# ADC_1_MUL.net
KiCad netlist of a schematic drawn in Altium Designer
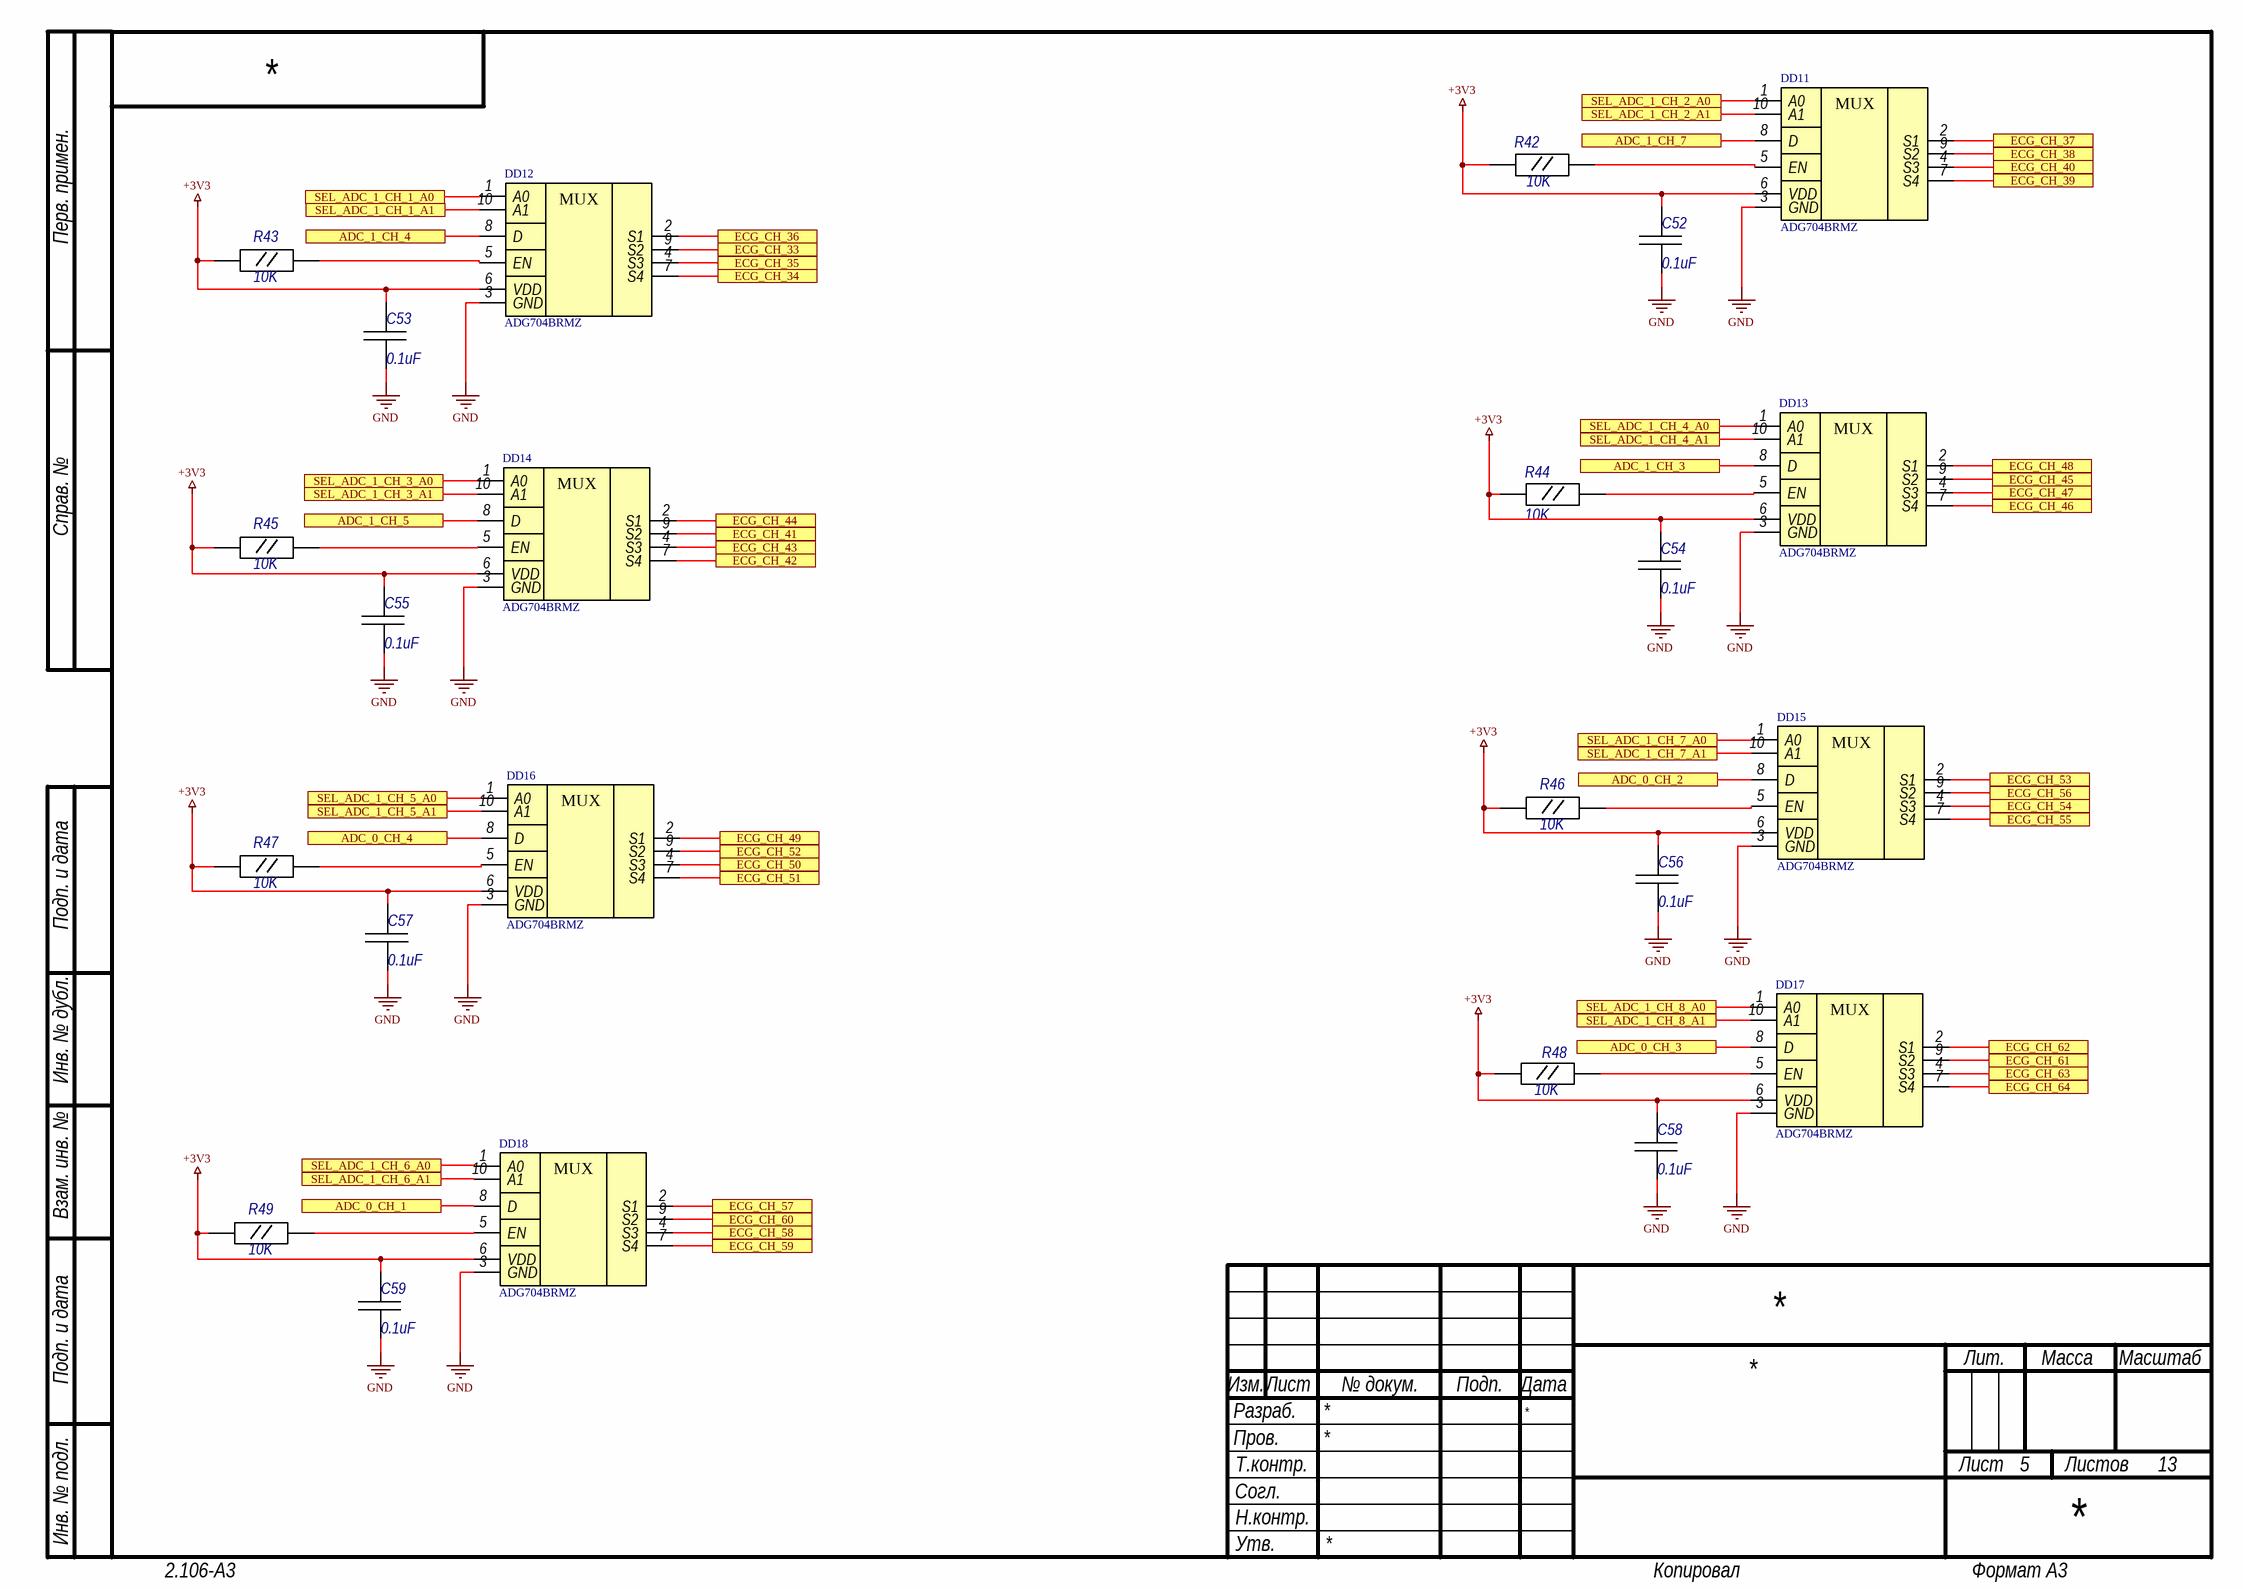
[diagram p0: ADC_1_MUL.SchDoc]

(export (version "E")
  (design (tool "Eeschema 10.0.6"))
  (components
    (comp (ref "C52")
      (value "0.1uF")
      (footprint "C0603")
      (description "Ceramic Capacitor SMD")
      (libsource (lib "") (part "CC_SMD_0603_1"))
    )
    (comp (ref "C53")
      (value "0.1uF")
      (footprint "C0603")
      (description "Ceramic Capacitor SMD")
      (libsource (lib "GOST") (part "CC_SMD_0603"))
    )
    (comp (ref "C54")
      (value "0.1uF")
      (footprint "C0603")
      (description "Ceramic Capacitor SMD")
      (libsource (lib "") (part "CC_SMD_0603_1"))
    )
    (comp (ref "C55")
      (value "0.1uF")
      (footprint "C0603")
      (description "Ceramic Capacitor SMD")
      (libsource (lib "GOST") (part "CC_SMD_0603"))
    )
    (comp (ref "C56")
      (value "0.1uF")
      (footprint "C0603")
      (description "Ceramic Capacitor SMD")
      (libsource (lib "GOST") (part "CC_SMD_0603"))
    )
    (comp (ref "C57")
      (value "0.1uF")
      (footprint "C0603")
      (description "Ceramic Capacitor SMD")
      (libsource (lib "GOST") (part "CC_SMD_0603"))
    )
    (comp (ref "C58")
      (value "0.1uF")
      (footprint "C0603")
      (description "Ceramic Capacitor SMD")
      (libsource (lib "GOST") (part "CC_SMD_0603"))
    )
    (comp (ref "C59")
      (value "0.1uF")
      (footprint "C0603")
      (description "Ceramic Capacitor SMD")
      (libsource (lib "GOST") (part "CC_SMD_0603"))
    )
    (comp (ref "DD11")
      (value "ADG704BRMZ")
      (footprint "MSOP-10")
      (description "4-Channel Multiplexer")
      (libsource (lib "GOST") (part "MUX_ADG704BRMZ"))
    )
    (comp (ref "DD12")
      (value "ADG704BRMZ")
      (footprint "MSOP-10")
      (description "4-Channel Multiplexer")
      (libsource (lib "GOST") (part "MUX_ADG704BRMZ"))
    )
    (comp (ref "DD13")
      (value "ADG704BRMZ")
      (footprint "MSOP-10")
      (description "4-Channel Multiplexer")
      (libsource (lib "GOST") (part "MUX_ADG704BRMZ"))
    )
    (comp (ref "DD14")
      (value "ADG704BRMZ")
      (footprint "MSOP-10")
      (description "4-Channel Multiplexer")
      (libsource (lib "GOST") (part "MUX_ADG704BRMZ"))
    )
    (comp (ref "DD15")
      (value "ADG704BRMZ")
      (footprint "MSOP-10")
      (description "4-Channel Multiplexer")
      (libsource (lib "GOST") (part "MUX_ADG704BRMZ"))
    )
    (comp (ref "DD16")
      (value "ADG704BRMZ")
      (footprint "MSOP-10")
      (description "4-Channel Multiplexer")
      (libsource (lib "GOST") (part "MUX_ADG704BRMZ"))
    )
    (comp (ref "DD17")
      (value "ADG704BRMZ")
      (footprint "MSOP-10")
      (description "4-Channel Multiplexer")
      (libsource (lib "GOST") (part "MUX_ADG704BRMZ"))
    )
    (comp (ref "DD18")
      (value "ADG704BRMZ")
      (footprint "MSOP-10")
      (description "4-Channel Multiplexer")
      (libsource (lib "GOST") (part "MUX_ADG704BRMZ"))
    )
    (comp (ref "R42")
      (value "10K")
      (footprint "R0603")
      (description "Resistor SMD")
      (libsource (lib "") (part "R0603_1"))
    )
    (comp (ref "R43")
      (value "10K")
      (footprint "R0603")
      (description "Resistor SMD")
      (libsource (lib "") (part "R0603_1"))
    )
    (comp (ref "R44")
      (value "10K")
      (footprint "R0603")
      (description "Resistor SMD")
      (libsource (lib "") (part "R0603_1"))
    )
    (comp (ref "R45")
      (value "10K")
      (footprint "R0603")
      (description "Resistor SMD")
      (libsource (lib "") (part "R0603_1"))
    )
    (comp (ref "R46")
      (value "10K")
      (footprint "R0603")
      (description "Resistor SMD")
      (libsource (lib "GOST") (part "R0603"))
    )
    (comp (ref "R47")
      (value "10K")
      (footprint "R0603")
      (description "Resistor SMD")
      (libsource (lib "GOST") (part "R0603"))
    )
    (comp (ref "R48")
      (value "10K")
      (footprint "R0603")
      (description "Resistor SMD")
      (libsource (lib "GOST") (part "R0603"))
    )
    (comp (ref "R49")
      (value "10K")
      (footprint "R0603")
      (description "Resistor SMD")
      (libsource (lib "GOST") (part "R0603"))
    )
  )
  (nets
    (net (code "1") (name "+3V3") (class "Default")
      (node (ref "C52") (pin "2") (pinfunction "2_2") (pintype "passive"))
      (node (ref "C53") (pin "2") (pinfunction "2_2") (pintype "passive"))
      (node (ref "C54") (pin "2") (pinfunction "2_2") (pintype "passive"))
      (node (ref "C55") (pin "2") (pinfunction "2_2") (pintype "passive"))
      (node (ref "C56") (pin "2") (pinfunction "2_2") (pintype "passive"))
      (node (ref "C57") (pin "2") (pinfunction "2_2") (pintype "passive"))
      (node (ref "C58") (pin "2") (pinfunction "2_2") (pintype "passive"))
      (node (ref "C59") (pin "2") (pinfunction "2_2") (pintype "passive"))
      (node (ref "DD11") (pin "6") (pinfunction "VDD_6") (pintype "passive"))
      (node (ref "DD12") (pin "6") (pinfunction "VDD_6") (pintype "passive"))
      (node (ref "DD13") (pin "6") (pinfunction "VDD_6") (pintype "passive"))
      (node (ref "DD14") (pin "6") (pinfunction "VDD_6") (pintype "passive"))
      (node (ref "DD15") (pin "6") (pinfunction "VDD_6") (pintype "passive"))
      (node (ref "DD16") (pin "6") (pinfunction "VDD_6") (pintype "passive"))
      (node (ref "DD17") (pin "6") (pinfunction "VDD_6") (pintype "passive"))
      (node (ref "DD18") (pin "6") (pinfunction "VDD_6") (pintype "passive"))
      (node (ref "R42") (pin "1") (pinfunction "1_1") (pintype "passive"))
      (node (ref "R43") (pin "1") (pinfunction "1_1") (pintype "passive"))
      (node (ref "R44") (pin "1") (pinfunction "1_1") (pintype "passive"))
      (node (ref "R45") (pin "1") (pinfunction "1_1") (pintype "passive"))
      (node (ref "R46") (pin "1") (pinfunction "1_1") (pintype "passive"))
      (node (ref "R47") (pin "1") (pinfunction "1_1") (pintype "passive"))
      (node (ref "R48") (pin "1") (pinfunction "1_1") (pintype "passive"))
      (node (ref "R49") (pin "1") (pinfunction "1_1") (pintype "passive"))
    )
    (net (code "2") (name "/ADC_0_CH_1") (class "Default")
      (node (ref "DD18") (pin "8") (pinfunction "D_8") (pintype "passive"))
    )
    (net (code "3") (name "/ADC_0_CH_2") (class "Default")
      (node (ref "DD15") (pin "8") (pinfunction "D_8") (pintype "passive"))
    )
    (net (code "4") (name "/ADC_0_CH_3") (class "Default")
      (node (ref "DD17") (pin "8") (pinfunction "D_8") (pintype "passive"))
    )
    (net (code "5") (name "/ADC_0_CH_4") (class "Default")
      (node (ref "DD16") (pin "8") (pinfunction "D_8") (pintype "passive"))
    )
    (net (code "6") (name "/ADC_1_CH_3") (class "Default")
      (node (ref "DD13") (pin "8") (pinfunction "D_8") (pintype "passive"))
    )
    (net (code "7") (name "/ADC_1_CH_4") (class "Default")
      (node (ref "DD12") (pin "8") (pinfunction "D_8") (pintype "passive"))
    )
    (net (code "8") (name "/ADC_1_CH_5") (class "Default")
      (node (ref "DD14") (pin "8") (pinfunction "D_8") (pintype "passive"))
    )
    (net (code "9") (name "/ADC_1_CH_7") (class "Default")
      (node (ref "DD11") (pin "8") (pinfunction "D_8") (pintype "passive"))
    )
    (net (code "10") (name "/ECG_CH_33") (class "Default")
      (node (ref "DD12") (pin "9") (pinfunction "S2_9") (pintype "passive"))
    )
    (net (code "11") (name "/ECG_CH_34") (class "Default")
      (node (ref "DD12") (pin "7") (pinfunction "S4_7") (pintype "passive"))
    )
    (net (code "12") (name "/ECG_CH_35") (class "Default")
      (node (ref "DD12") (pin "4") (pinfunction "S3_4") (pintype "passive"))
    )
    (net (code "13") (name "/ECG_CH_36") (class "Default")
      (node (ref "DD12") (pin "2") (pinfunction "S1_2") (pintype "passive"))
    )
    (net (code "14") (name "/ECG_CH_37") (class "Default")
      (node (ref "DD11") (pin "2") (pinfunction "S1_2") (pintype "passive"))
    )
    (net (code "15") (name "/ECG_CH_38") (class "Default")
      (node (ref "DD11") (pin "9") (pinfunction "S2_9") (pintype "passive"))
    )
    (net (code "16") (name "/ECG_CH_39") (class "Default")
      (node (ref "DD11") (pin "7") (pinfunction "S4_7") (pintype "passive"))
    )
    (net (code "17") (name "/ECG_CH_40") (class "Default")
      (node (ref "DD11") (pin "4") (pinfunction "S3_4") (pintype "passive"))
    )
    (net (code "18") (name "/ECG_CH_41") (class "Default")
      (node (ref "DD14") (pin "9") (pinfunction "S2_9") (pintype "passive"))
    )
    (net (code "19") (name "/ECG_CH_42") (class "Default")
      (node (ref "DD14") (pin "7") (pinfunction "S4_7") (pintype "passive"))
    )
    (net (code "20") (name "/ECG_CH_43") (class "Default")
      (node (ref "DD14") (pin "4") (pinfunction "S3_4") (pintype "passive"))
    )
    (net (code "21") (name "/ECG_CH_44") (class "Default")
      (node (ref "DD14") (pin "2") (pinfunction "S1_2") (pintype "passive"))
    )
    (net (code "22") (name "/ECG_CH_45") (class "Default")
      (node (ref "DD13") (pin "9") (pinfunction "S2_9") (pintype "passive"))
    )
    (net (code "23") (name "/ECG_CH_46") (class "Default")
      (node (ref "DD13") (pin "7") (pinfunction "S4_7") (pintype "passive"))
    )
    (net (code "24") (name "/ECG_CH_47") (class "Default")
      (node (ref "DD13") (pin "4") (pinfunction "S3_4") (pintype "passive"))
    )
    (net (code "25") (name "/ECG_CH_48") (class "Default")
      (node (ref "DD13") (pin "2") (pinfunction "S1_2") (pintype "passive"))
    )
    (net (code "26") (name "/ECG_CH_49") (class "Default")
      (node (ref "DD16") (pin "2") (pinfunction "S1_2") (pintype "passive"))
    )
    (net (code "27") (name "/ECG_CH_50") (class "Default")
      (node (ref "DD16") (pin "4") (pinfunction "S3_4") (pintype "passive"))
    )
    (net (code "28") (name "/ECG_CH_51") (class "Default")
      (node (ref "DD16") (pin "7") (pinfunction "S4_7") (pintype "passive"))
    )
    (net (code "29") (name "/ECG_CH_52") (class "Default")
      (node (ref "DD16") (pin "9") (pinfunction "S2_9") (pintype "passive"))
    )
    (net (code "30") (name "/ECG_CH_53") (class "Default")
      (node (ref "DD15") (pin "2") (pinfunction "S1_2") (pintype "passive"))
    )
    (net (code "31") (name "/ECG_CH_54") (class "Default")
      (node (ref "DD15") (pin "4") (pinfunction "S3_4") (pintype "passive"))
    )
    (net (code "32") (name "/ECG_CH_55") (class "Default")
      (node (ref "DD15") (pin "7") (pinfunction "S4_7") (pintype "passive"))
    )
    (net (code "33") (name "/ECG_CH_56") (class "Default")
      (node (ref "DD15") (pin "9") (pinfunction "S2_9") (pintype "passive"))
    )
    (net (code "34") (name "/ECG_CH_57") (class "Default")
      (node (ref "DD18") (pin "2") (pinfunction "S1_2") (pintype "passive"))
    )
    (net (code "35") (name "/ECG_CH_58") (class "Default")
      (node (ref "DD18") (pin "4") (pinfunction "S3_4") (pintype "passive"))
    )
    (net (code "36") (name "/ECG_CH_59") (class "Default")
      (node (ref "DD18") (pin "7") (pinfunction "S4_7") (pintype "passive"))
    )
    (net (code "37") (name "/ECG_CH_60") (class "Default")
      (node (ref "DD18") (pin "9") (pinfunction "S2_9") (pintype "passive"))
    )
    (net (code "38") (name "/ECG_CH_61") (class "Default")
      (node (ref "DD17") (pin "9") (pinfunction "S2_9") (pintype "passive"))
    )
    (net (code "39") (name "/ECG_CH_62") (class "Default")
      (node (ref "DD17") (pin "2") (pinfunction "S1_2") (pintype "passive"))
    )
    (net (code "40") (name "/ECG_CH_63") (class "Default")
      (node (ref "DD17") (pin "4") (pinfunction "S3_4") (pintype "passive"))
    )
    (net (code "41") (name "/ECG_CH_64") (class "Default")
      (node (ref "DD17") (pin "7") (pinfunction "S4_7") (pintype "passive"))
    )
    (net (code "42") (name "/SEL_ADC_1_CH_1_A0") (class "Default")
      (node (ref "DD12") (pin "1") (pinfunction "A0_1") (pintype "passive"))
    )
    (net (code "43") (name "/SEL_ADC_1_CH_1_A1") (class "Default")
      (node (ref "DD12") (pin "10") (pinfunction "A1_10") (pintype "passive"))
    )
    (net (code "44") (name "/SEL_ADC_1_CH_2_A0") (class "Default")
      (node (ref "DD11") (pin "1") (pinfunction "A0_1") (pintype "passive"))
    )
    (net (code "45") (name "/SEL_ADC_1_CH_2_A1") (class "Default")
      (node (ref "DD11") (pin "10") (pinfunction "A1_10") (pintype "passive"))
    )
    (net (code "46") (name "/SEL_ADC_1_CH_3_A0") (class "Default")
      (node (ref "DD14") (pin "1") (pinfunction "A0_1") (pintype "passive"))
    )
    (net (code "47") (name "/SEL_ADC_1_CH_3_A1") (class "Default")
      (node (ref "DD14") (pin "10") (pinfunction "A1_10") (pintype "passive"))
    )
    (net (code "48") (name "/SEL_ADC_1_CH_4_A0") (class "Default")
      (node (ref "DD13") (pin "1") (pinfunction "A0_1") (pintype "passive"))
    )
    (net (code "49") (name "/SEL_ADC_1_CH_4_A1") (class "Default")
      (node (ref "DD13") (pin "10") (pinfunction "A1_10") (pintype "passive"))
    )
    (net (code "50") (name "/SEL_ADC_1_CH_5_A0") (class "Default")
      (node (ref "DD16") (pin "1") (pinfunction "A0_1") (pintype "passive"))
    )
    (net (code "51") (name "/SEL_ADC_1_CH_5_A1") (class "Default")
      (node (ref "DD16") (pin "10") (pinfunction "A1_10") (pintype "passive"))
    )
    (net (code "52") (name "/SEL_ADC_1_CH_6_A0") (class "Default")
      (node (ref "DD18") (pin "1") (pinfunction "A0_1") (pintype "passive"))
    )
    (net (code "53") (name "/SEL_ADC_1_CH_6_A1") (class "Default")
      (node (ref "DD18") (pin "10") (pinfunction "A1_10") (pintype "passive"))
    )
    (net (code "54") (name "/SEL_ADC_1_CH_7_A0") (class "Default")
      (node (ref "DD15") (pin "1") (pinfunction "A0_1") (pintype "passive"))
    )
    (net (code "55") (name "/SEL_ADC_1_CH_7_A1") (class "Default")
      (node (ref "DD15") (pin "10") (pinfunction "A1_10") (pintype "passive"))
    )
    (net (code "56") (name "/SEL_ADC_1_CH_8_A0") (class "Default")
      (node (ref "DD17") (pin "1") (pinfunction "A0_1") (pintype "passive"))
    )
    (net (code "57") (name "/SEL_ADC_1_CH_8_A1") (class "Default")
      (node (ref "DD17") (pin "10") (pinfunction "A1_10") (pintype "passive"))
    )
    (net (code "58") (name "GND") (class "Default")
      (node (ref "C52") (pin "1") (pinfunction "1_1") (pintype "passive"))
      (node (ref "C53") (pin "1") (pinfunction "1_1") (pintype "passive"))
      (node (ref "C54") (pin "1") (pinfunction "1_1") (pintype "passive"))
      (node (ref "C55") (pin "1") (pinfunction "1_1") (pintype "passive"))
      (node (ref "C56") (pin "1") (pinfunction "1_1") (pintype "passive"))
      (node (ref "C57") (pin "1") (pinfunction "1_1") (pintype "passive"))
      (node (ref "C58") (pin "1") (pinfunction "1_1") (pintype "passive"))
      (node (ref "C59") (pin "1") (pinfunction "1_1") (pintype "passive"))
      (node (ref "DD11") (pin "3") (pinfunction "GND_3") (pintype "passive"))
      (node (ref "DD12") (pin "3") (pinfunction "GND_3") (pintype "passive"))
      (node (ref "DD13") (pin "3") (pinfunction "GND_3") (pintype "passive"))
      (node (ref "DD14") (pin "3") (pinfunction "GND_3") (pintype "passive"))
      (node (ref "DD15") (pin "3") (pinfunction "GND_3") (pintype "passive"))
      (node (ref "DD16") (pin "3") (pinfunction "GND_3") (pintype "passive"))
      (node (ref "DD17") (pin "3") (pinfunction "GND_3") (pintype "passive"))
      (node (ref "DD18") (pin "3") (pinfunction "GND_3") (pintype "passive"))
    )
    (net (code "59") (name "Net-(DD11-EN)") (class "Default")
      (node (ref "DD11") (pin "5") (pinfunction "EN_5") (pintype "passive"))
      (node (ref "R42") (pin "2") (pinfunction "2_2") (pintype "passive"))
    )
    (net (code "60") (name "Net-(DD12-EN)") (class "Default")
      (node (ref "DD12") (pin "5") (pinfunction "EN_5") (pintype "passive"))
      (node (ref "R43") (pin "2") (pinfunction "2_2") (pintype "passive"))
    )
    (net (code "61") (name "Net-(DD13-EN)") (class "Default")
      (node (ref "DD13") (pin "5") (pinfunction "EN_5") (pintype "passive"))
      (node (ref "R44") (pin "2") (pinfunction "2_2") (pintype "passive"))
    )
    (net (code "62") (name "Net-(DD14-EN)") (class "Default")
      (node (ref "DD14") (pin "5") (pinfunction "EN_5") (pintype "passive"))
      (node (ref "R45") (pin "2") (pinfunction "2_2") (pintype "passive"))
    )
    (net (code "63") (name "Net-(DD15-EN)") (class "Default")
      (node (ref "DD15") (pin "5") (pinfunction "EN_5") (pintype "passive"))
      (node (ref "R46") (pin "2") (pinfunction "2_2") (pintype "passive"))
    )
    (net (code "64") (name "Net-(DD16-EN)") (class "Default")
      (node (ref "DD16") (pin "5") (pinfunction "EN_5") (pintype "passive"))
      (node (ref "R47") (pin "2") (pinfunction "2_2") (pintype "passive"))
    )
    (net (code "65") (name "Net-(DD17-EN)") (class "Default")
      (node (ref "DD17") (pin "5") (pinfunction "EN_5") (pintype "passive"))
      (node (ref "R48") (pin "2") (pinfunction "2_2") (pintype "passive"))
    )
    (net (code "66") (name "Net-(DD18-EN)") (class "Default")
      (node (ref "DD18") (pin "5") (pinfunction "EN_5") (pintype "passive"))
      (node (ref "R49") (pin "2") (pinfunction "2_2") (pintype "passive"))
    )
  )
)
